# RS232_Garbage.net
KiCad netlist of a schematic drawn in Altium Designer
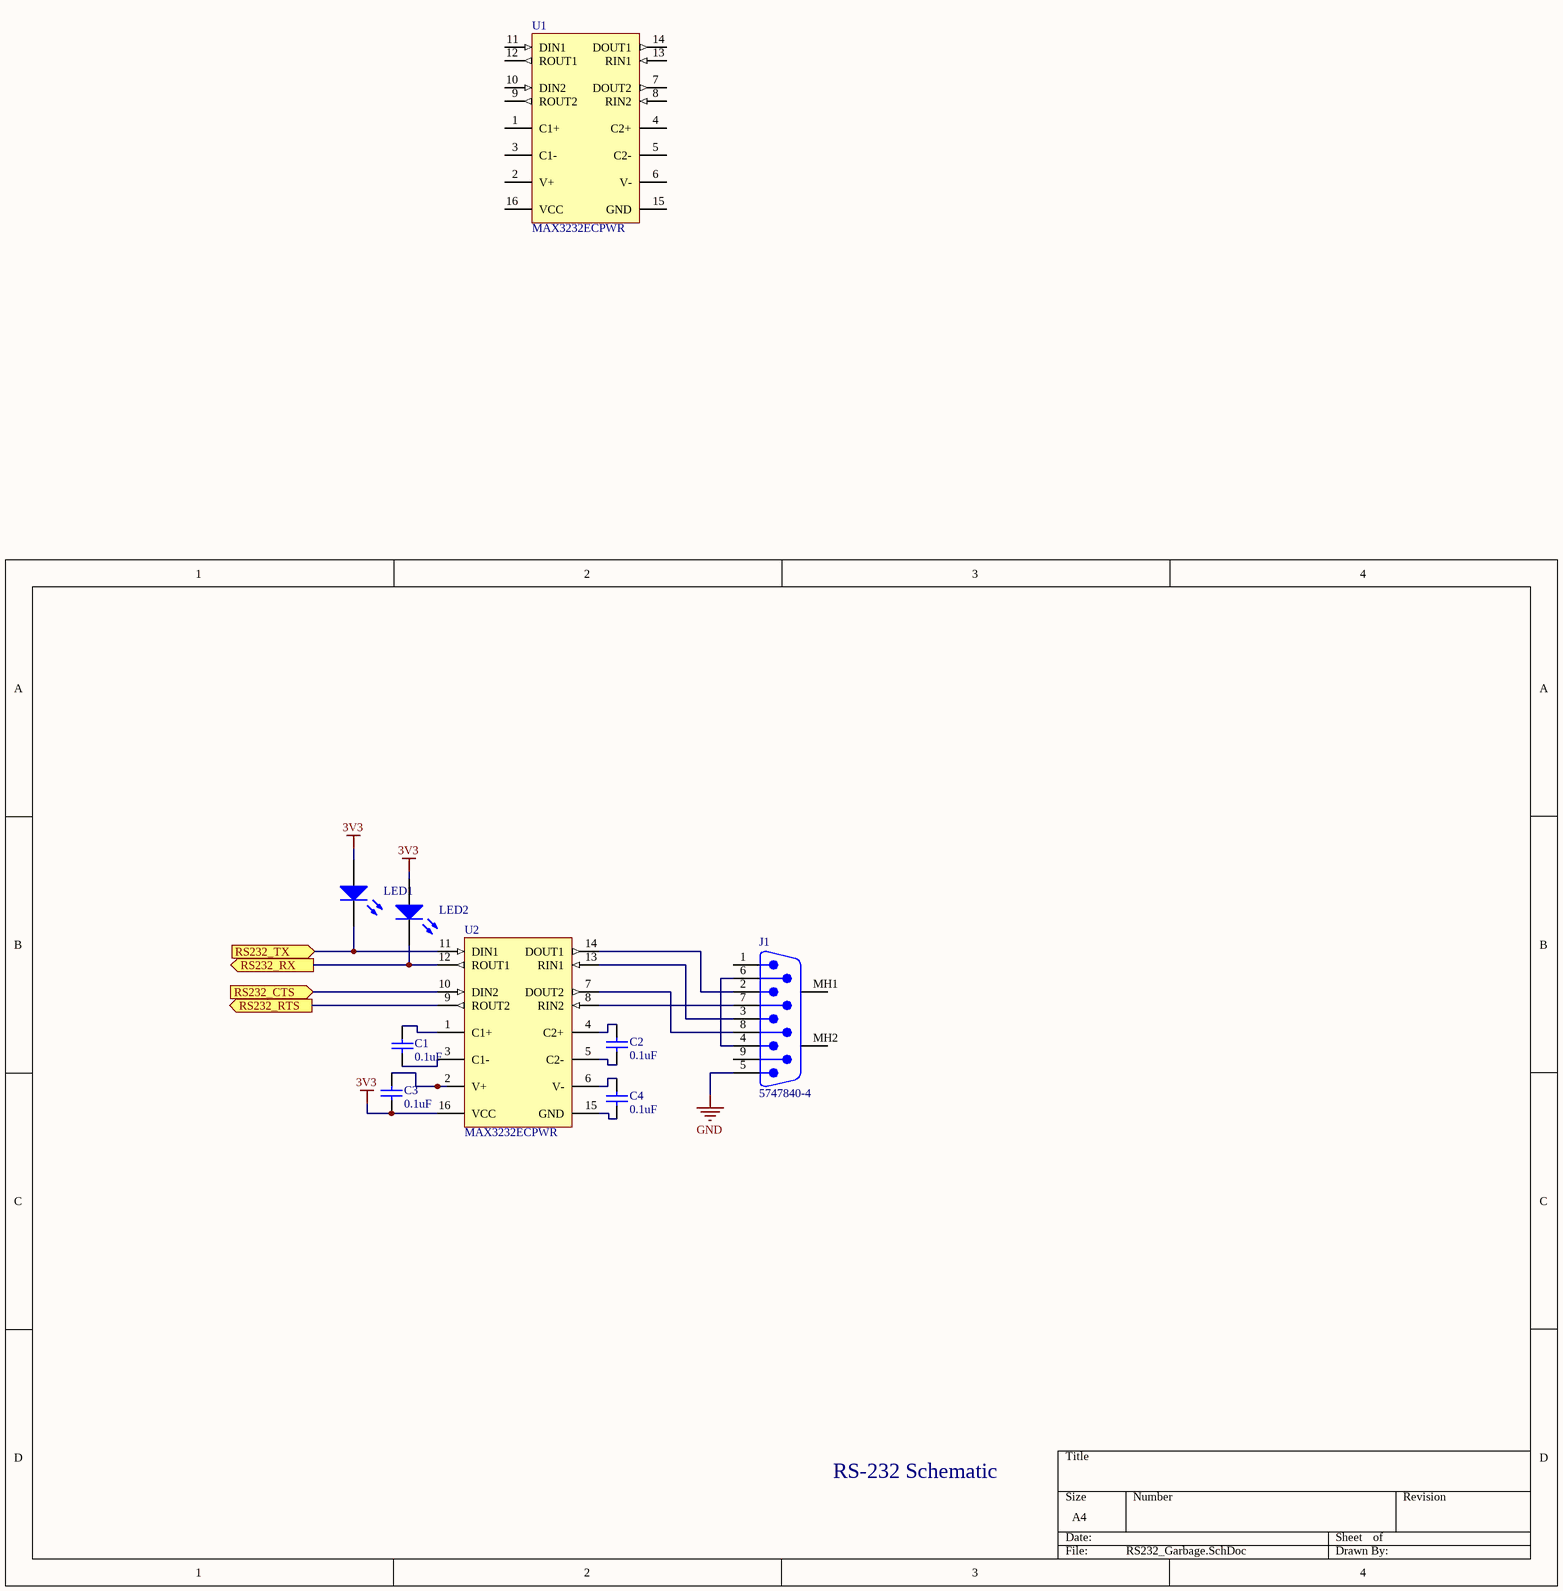
[diagram p0: RS232_Garbage.SchDoc]

(export (version "E")
  (design (tool "Eeschema 10.0.6"))
  (components
    (comp (ref "C1")
      (value "0.1uF")
      (footprint "CAPC1608X90X35LL15T15")
      (description "Chip Capacitor, 100 nF, +/- 10%, 50 V, -55 to 125 degC, 0603 (1608 Metric), RoHS, Tape and Reel")
      (fields (field (name "TOLERANCE") "10%"))
      (libsource (lib "Altium Content Vault") (part "CAP-NP-2"))
    )
    (comp (ref "C2")
      (value "0.1uF")
      (footprint "CAPC1608X90X35LL15T15")
      (description "Chip Capacitor, 100 nF, +/- 10%, 50 V, -55 to 125 degC, 0603 (1608 Metric), RoHS, Tape and Reel")
      (fields (field (name "TOLERANCE") "10%"))
      (libsource (lib "Altium Content Vault") (part "CAP-NP-2"))
    )
    (comp (ref "C3")
      (value "0.1uF")
      (footprint "CAPC1608X90X35ML15T15")
      (description "Chip Capacitor, 100 nF, +/- 10%, 50 V, -55 to 125 degC, 0603 (1608 Metric), RoHS, Tape and Reel")
      (fields (field (name "TOLERANCE") "10%"))
      (libsource (lib "Altium Content Vault") (part "CAP-NP-2"))
    )
    (comp (ref "C4")
      (value "0.1uF")
      (footprint "CAPC1608X90X35LL15T15")
      (description "Chip Capacitor, 100 nF, +/- 10%, 50 V, -55 to 125 degC, 0603 (1608 Metric), RoHS, Tape and Reel")
      (fields (field (name "TOLERANCE") "10%"))
      (libsource (lib "Altium Content Vault") (part "CAP-NP-2"))
    )
    (comp (ref "J1")
      (value "5747840-4")
      (footprint "TECO-5747840-4_V")
      (fields (field (name "MANUFACTURER") "TE Connectivity"))
      (libsource (lib "Altium Content Vault") (part "CN-2S-2M-D9"))
    )
    (comp (ref "LED1")
      (value "~")
      (footprint "1204")
      (description "SMD Side view mono-color Chip LED-Round , WL-SMSW, Green")
      (fields (field (name "PARTNUMBER") "155124GS73200") (field (name "MANUFACTURER") "Wuerth Elektronik"))
      (libsource (lib "Altium Content Vault") (part "WE-LED_K1A2-2"))
    )
    (comp (ref "LED2")
      (value "~")
      (footprint "1204")
      (description "SMD Side view mono-color Chip LED-Round , WL-SMSW, Green")
      (fields (field (name "PARTNUMBER") "155124GS73200") (field (name "MANUFACTURER") "Wuerth Elektronik"))
      (libsource (lib "Altium Content Vault") (part "WE-LED_K1A2-2"))
    )
    (comp (ref "U1")
      (value "MAX3232ECPWR")
      (footprint "PW0016A_M")
      (libsource (lib "Altium Content Vault") (part "TI-MAX3232E-TSSOP_PW-16"))
    )
    (comp (ref "U2")
      (value "MAX3232ECPWR")
      (footprint "PW0016A_M")
      (libsource (lib "Altium Content Vault") (part "TI-MAX3232E-TSSOP_PW-16"))
    )
  )
  (nets
    (net (code "1") (name "/RS232_CTS") (class "Default")
      (node (ref "U2") (pin "10") (pinfunction "DIN2_10") (pintype "input"))
    )
    (net (code "2") (name "/RS232_RTS") (class "Default")
      (node (ref "U2") (pin "9") (pinfunction "ROUT2_9") (pintype "output"))
    )
    (net (code "3") (name "/RS232_RX") (class "Default")
      (node (ref "LED2") (pin "1") (pinfunction "K_1") (pintype "passive"))
      (node (ref "U2") (pin "12") (pinfunction "ROUT1_12") (pintype "output"))
    )
    (net (code "4") (name "/RS232_TX") (class "Default")
      (node (ref "LED1") (pin "1") (pinfunction "K_1") (pintype "passive"))
      (node (ref "U2") (pin "11") (pinfunction "DIN1_11") (pintype "input"))
    )
    (net (code "5") (name "3V3") (class "Default")
      (node (ref "C3") (pin "1") (pinfunction "1_1") (pintype "passive"))
      (node (ref "LED1") (pin "2") (pinfunction "A_2") (pintype "passive"))
      (node (ref "LED2") (pin "2") (pinfunction "A_2") (pintype "passive"))
      (node (ref "U2") (pin "16") (pinfunction "VCC_16") (pintype "power_in"))
    )
    (net (code "6") (name "GND") (class "Default")
      (node (ref "J1") (pin "5") (pinfunction "5_5") (pintype "passive"))
    )
    (net (code "7") (name "Net-(J1-Pad4)") (class "Default")
      (node (ref "J1") (pin "4") (pinfunction "4_4") (pintype "passive"))
      (node (ref "J1") (pin "6") (pinfunction "6_6") (pintype "passive"))
    )
    (net (code "8") (name "Net-(U2-C1+)") (class "Default")
      (node (ref "C1") (pin "2") (pinfunction "2_2") (pintype "passive"))
      (node (ref "U2") (pin "1") (pinfunction "C1+_1") (pintype "passive"))
    )
    (net (code "9") (name "Net-(U2-C1-)") (class "Default")
      (node (ref "C1") (pin "1") (pinfunction "1_1") (pintype "passive"))
      (node (ref "U2") (pin "3") (pinfunction "C1-_3") (pintype "passive"))
    )
    (net (code "10") (name "Net-(U2-C2+)") (class "Default")
      (node (ref "C2") (pin "2") (pinfunction "2_2") (pintype "passive"))
      (node (ref "U2") (pin "4") (pinfunction "C2+_4") (pintype "passive"))
    )
    (net (code "11") (name "Net-(U2-C2-)") (class "Default")
      (node (ref "C2") (pin "1") (pinfunction "1_1") (pintype "passive"))
      (node (ref "U2") (pin "5") (pinfunction "C2-_5") (pintype "passive"))
    )
    (net (code "12") (name "Net-(U2-DOUT1)") (class "Default")
      (node (ref "J1") (pin "2") (pinfunction "2_2") (pintype "passive"))
      (node (ref "U2") (pin "14") (pinfunction "DOUT1_14") (pintype "output"))
    )
    (net (code "13") (name "Net-(U2-DOUT2)") (class "Default")
      (node (ref "J1") (pin "8") (pinfunction "8_8") (pintype "passive"))
      (node (ref "U2") (pin "7") (pinfunction "DOUT2_7") (pintype "output"))
    )
    (net (code "14") (name "Net-(U2-GND)") (class "Default")
      (node (ref "C4") (pin "1") (pinfunction "1_1") (pintype "passive"))
      (node (ref "U2") (pin "15") (pinfunction "GND_15") (pintype "power_in"))
    )
    (net (code "15") (name "Net-(U2-RIN1)") (class "Default")
      (node (ref "J1") (pin "3") (pinfunction "3_3") (pintype "passive"))
      (node (ref "U2") (pin "13") (pinfunction "RIN1_13") (pintype "input"))
    )
    (net (code "16") (name "Net-(U2-RIN2)") (class "Default")
      (node (ref "J1") (pin "7") (pinfunction "7_7") (pintype "passive"))
      (node (ref "U2") (pin "8") (pinfunction "RIN2_8") (pintype "input"))
    )
    (net (code "17") (name "Net-(U2-V+)") (class "Default")
      (node (ref "C3") (pin "2") (pinfunction "2_2") (pintype "passive"))
      (node (ref "U2") (pin "2") (pinfunction "V+_2") (pintype "power_in"))
    )
    (net (code "18") (name "Net-(U2-V-)") (class "Default")
      (node (ref "C4") (pin "2") (pinfunction "2_2") (pintype "passive"))
      (node (ref "U2") (pin "6") (pinfunction "V-_6") (pintype "power_in"))
    )
    (net (code "19") (name "unconnected-(J1-Pad1)") (class "Default")
      (node (ref "J1") (pin "1") (pinfunction "1_1") (pintype "passive"))
    )
    (net (code "20") (name "unconnected-(J1-Pad9)") (class "Default")
      (node (ref "J1") (pin "9") (pinfunction "9_9") (pintype "passive"))
    )
    (net (code "21") (name "unconnected-(J1-PadMH1)") (class "Default")
      (node (ref "J1") (pin "MH1") (pinfunction "MH1_MH1") (pintype "passive"))
    )
    (net (code "22") (name "unconnected-(J1-PadMH2)") (class "Default")
      (node (ref "J1") (pin "MH2") (pinfunction "MH2_MH2") (pintype "passive"))
    )
    (net (code "23") (name "unconnected-(U1-C1+-Pad1)") (class "Default")
      (node (ref "U1") (pin "1") (pinfunction "C1+_1") (pintype "passive"))
    )
    (net (code "24") (name "unconnected-(U1-C1--Pad3)") (class "Default")
      (node (ref "U1") (pin "3") (pinfunction "C1-_3") (pintype "passive"))
    )
    (net (code "25") (name "unconnected-(U1-C2+-Pad4)") (class "Default")
      (node (ref "U1") (pin "4") (pinfunction "C2+_4") (pintype "passive"))
    )
    (net (code "26") (name "unconnected-(U1-C2--Pad5)") (class "Default")
      (node (ref "U1") (pin "5") (pinfunction "C2-_5") (pintype "passive"))
    )
    (net (code "27") (name "unconnected-(U1-DIN1-Pad11)") (class "Default")
      (node (ref "U1") (pin "11") (pinfunction "DIN1_11") (pintype "input"))
    )
    (net (code "28") (name "unconnected-(U1-DIN2-Pad10)") (class "Default")
      (node (ref "U1") (pin "10") (pinfunction "DIN2_10") (pintype "input"))
    )
    (net (code "29") (name "unconnected-(U1-DOUT1-Pad14)") (class "Default")
      (node (ref "U1") (pin "14") (pinfunction "DOUT1_14") (pintype "output"))
    )
    (net (code "30") (name "unconnected-(U1-DOUT2-Pad7)") (class "Default")
      (node (ref "U1") (pin "7") (pinfunction "DOUT2_7") (pintype "output"))
    )
    (net (code "31") (name "unconnected-(U1-GND-Pad15)") (class "Default")
      (node (ref "U1") (pin "15") (pinfunction "GND_15") (pintype "power_in"))
    )
    (net (code "32") (name "unconnected-(U1-RIN1-Pad13)") (class "Default")
      (node (ref "U1") (pin "13") (pinfunction "RIN1_13") (pintype "input"))
    )
    (net (code "33") (name "unconnected-(U1-RIN2-Pad8)") (class "Default")
      (node (ref "U1") (pin "8") (pinfunction "RIN2_8") (pintype "input"))
    )
    (net (code "34") (name "unconnected-(U1-ROUT1-Pad12)") (class "Default")
      (node (ref "U1") (pin "12") (pinfunction "ROUT1_12") (pintype "output"))
    )
    (net (code "35") (name "unconnected-(U1-ROUT2-Pad9)") (class "Default")
      (node (ref "U1") (pin "9") (pinfunction "ROUT2_9") (pintype "output"))
    )
    (net (code "36") (name "unconnected-(U1-V+-Pad2)") (class "Default")
      (node (ref "U1") (pin "2") (pinfunction "V+_2") (pintype "power_in"))
    )
    (net (code "37") (name "unconnected-(U1-V--Pad6)") (class "Default")
      (node (ref "U1") (pin "6") (pinfunction "V-_6") (pintype "power_in"))
    )
    (net (code "38") (name "unconnected-(U1-VCC-Pad16)") (class "Default")
      (node (ref "U1") (pin "16") (pinfunction "VCC_16") (pintype "power_in"))
    )
  )
)
